# main_sheet.net
KiCad netlist of a schematic drawn in Altium Designer
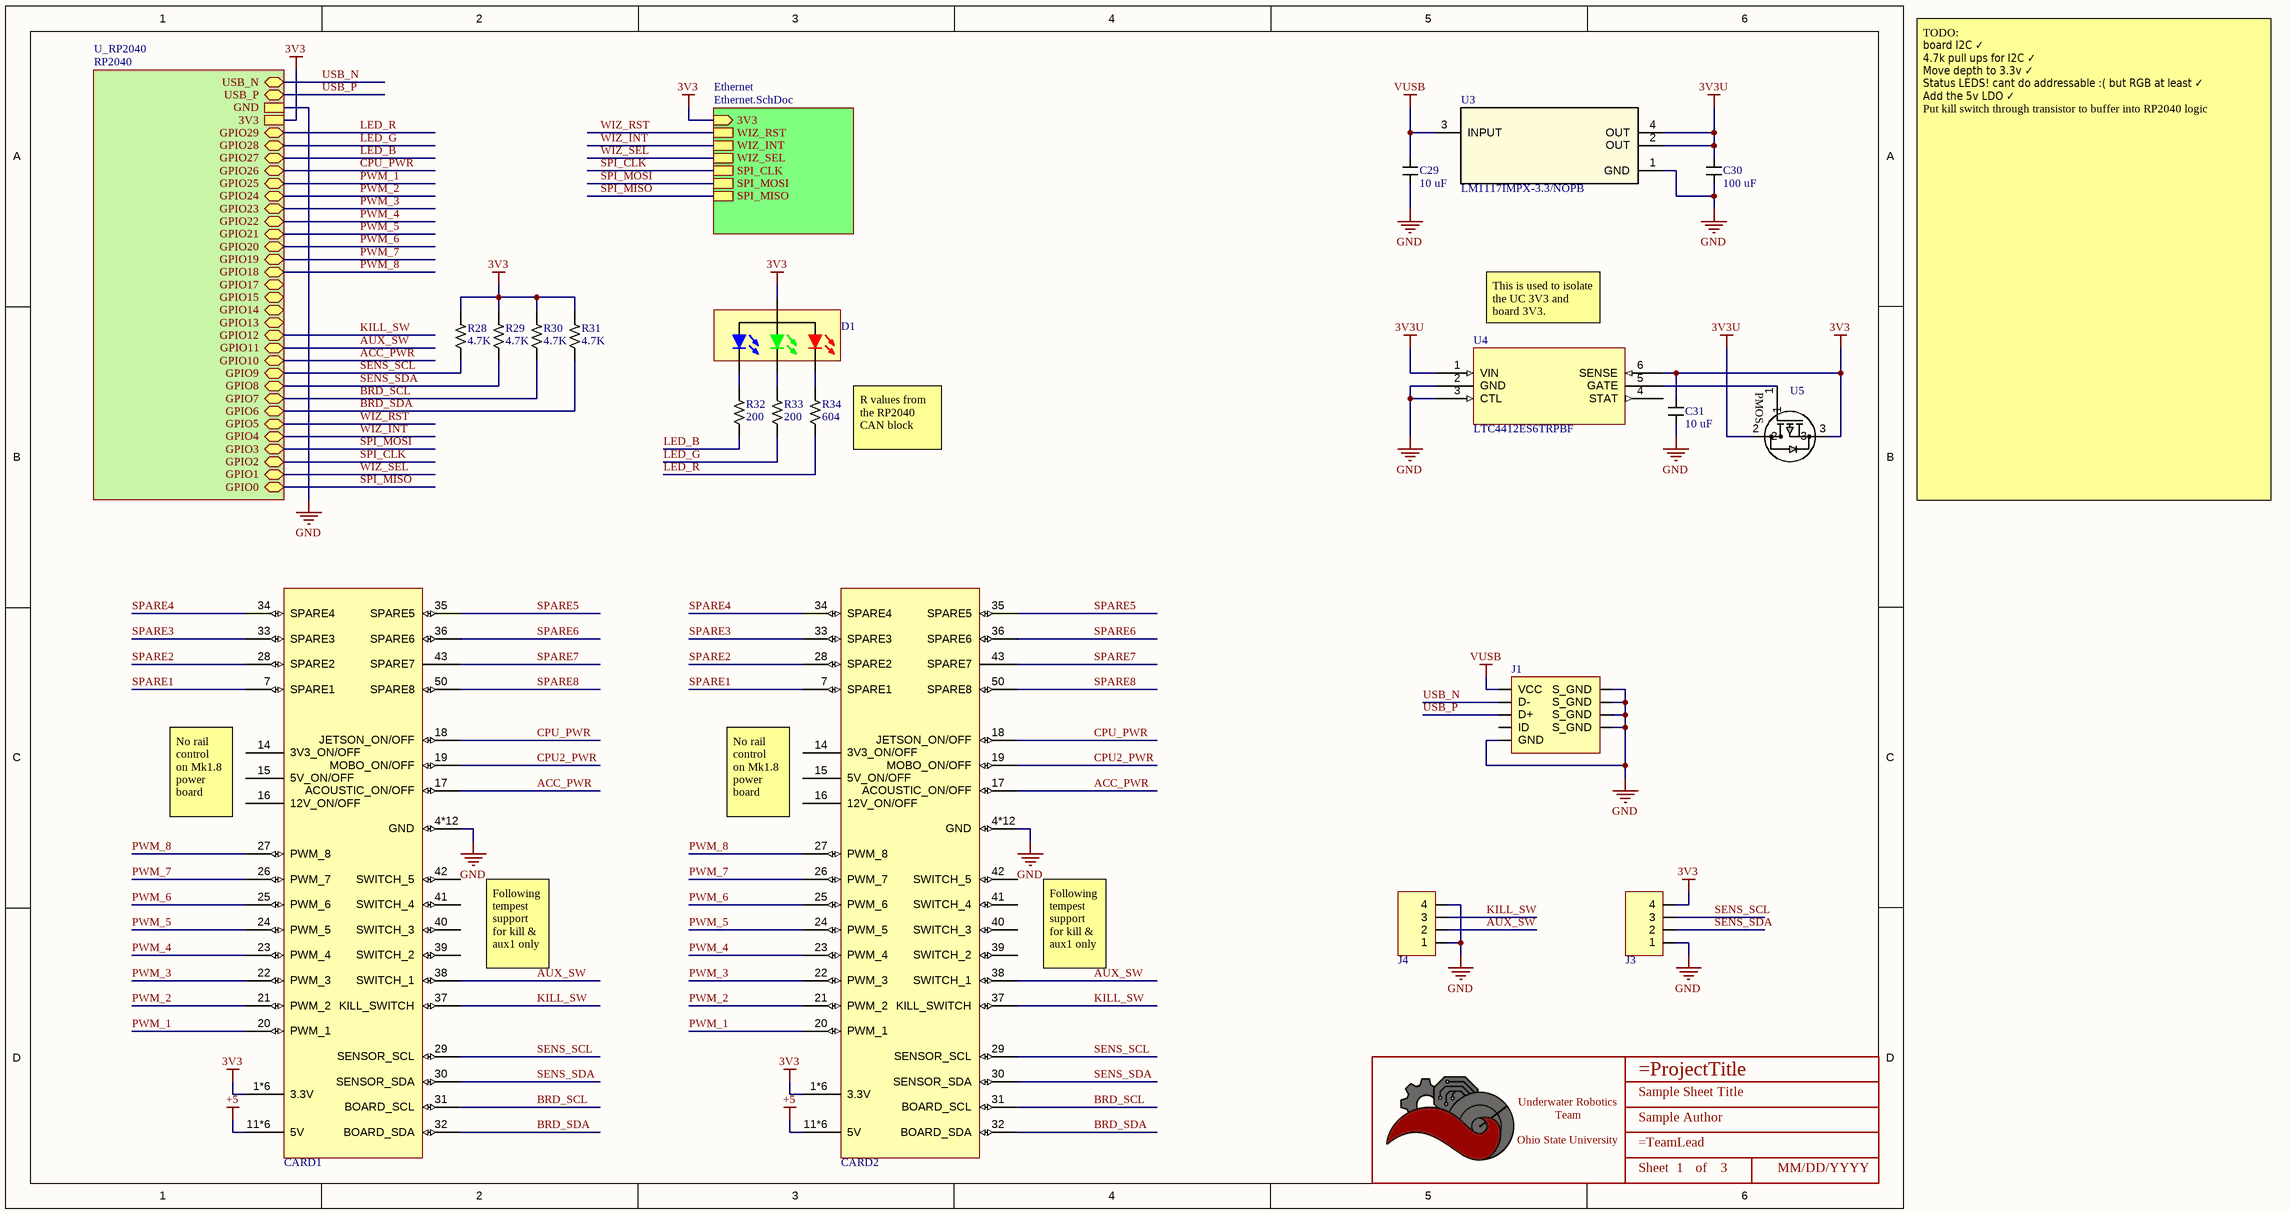
[diagram p0: main_sheet.SchDoc]

(export (version "E")
  (design (tool "Eeschema 10.0.6"))
  (components
    (comp (ref "*")
      (value "Title_Block")
      (footprint "LOGO")
      (description "UWRT Schematic Title Block Template\r\n\r\nCreated June 2021, Dylan Trainor")
      (libsource (lib "UWRT") (part "Title_Block"))
    )
    (comp (ref "C29")
      (value "10uF Ceramic 6.3V")
      (footprint "CAPACITOR_0603")
      (description "Cap 10uF 6.3V +/-20%\r\nCeramic 0603")
      (fields
        (field (name "TOLERANCE") "+/- 20%")
        (field (name "VOLTAGE") "6.3V")
        (field (name "VALUE (UF)") "10 uF")
        (field (name "MADE BY") "Flip B")
      )
      (libsource (lib "Capacitors") (part "CAPACITOR_10uF_0603"))
    )
    (comp (ref "C30")
      (value "100uF Ceramic 6.3V")
      (footprint "CAPACITOR_0603")
      (description "Cap 100uF 6.3V +/-20%\r\nCeramic 0603")
      (fields
        (field (name "TOLERANCE") "+/- 20%")
        (field (name "VOLTAGE") "6.3V")
        (field (name "VALUE (UF)") "100 uF")
        (field (name "MADE BY") "Dylan Trainor")
      )
      (libsource (lib "Capacitors") (part "CAPACITOR_100uF_0603"))
    )
    (comp (ref "C31")
      (value "10uF Ceramic 6.3V")
      (footprint "CAPACITOR_0603")
      (description "Cap 10uF 6.3V +/-20%\r\nCeramic 0603")
      (fields
        (field (name "TOLERANCE") "+/- 20%")
        (field (name "VOLTAGE") "6.3V")
        (field (name "VALUE (UF)") "10 uF")
        (field (name "MADE BY") "Flip B")
      )
      (libsource (lib "Capacitors") (part "CAPACITOR_10uF_0603"))
    )
    (comp (ref "CARD1")
      (value "BACKPLANE_EDGE_SOCKET")
      (footprint "SOCKET_BACKPLANE_EDGE_CONN")
      (description "Backplane Edge Socket")
      (fields (field (name "MADE BY") "Robert Pafford"))
      (libsource (lib "Connectors") (part "BACKPLANE_EDGE_SOCKET"))
    )
    (comp (ref "CARD2")
      (value "BACKPLANE_EDGE_SOCKET")
      (footprint "SOCKET_BACKPLANE_EDGE_CONN")
      (description "Backplane Edge Socket")
      (fields (field (name "MADE BY") "Robert Pafford"))
      (libsource (lib "Connectors") (part "BACKPLANE_EDGE_SOCKET"))
    )
    (comp (ref "D1")
      (value "EAST1616RGBB4")
      (footprint "LED_0606_4SMD")
      (description "LED RGB CLEAR 4SMD")
      (fields (field (name "MADE BY") "Robert Pafford"))
      (libsource (lib "Diodes") (part "LED_RGB_4SMD"))
    )
    (comp (ref "J1")
      (value "USB_MICRO R/A")
      (footprint "CONN_MINIUSB")
      (description "Amphenol Micro USB-B\r\nUSB2.0 5 Pin Right Angle SMD")
      (fields (field (name "MANUFACTURER") "Amphenol") (field (name "CREATED BY") "Flip B"))
      (libsource (lib "Connectors") (part "CONN_MICROUSB"))
    )
    (comp (ref "J3")
      (value "4 POS R/A")
      (footprint "CONN_MOLEX_MINIFIT JR_4 POS_R/A")
      (description "Molex Minifit Jr. 5569 \r\n4 Pos R/A Natural")
      (fields (field (name "MANUFACTURER") "Molex") (field (name "CREATED BY") "Flip B"))
      (libsource (lib "Connectors") (part "CONN_MOLEX_MINIFIT JR_4POS_R/A"))
    )
    (comp (ref "J4")
      (value "4 POS R/A")
      (footprint "CONN_MOLEX_MINIFIT JR_4 POS_R/A")
      (description "Molex Minifit Jr. 5569 \r\n4 Pos R/A Natural")
      (fields (field (name "MANUFACTURER") "Molex") (field (name "CREATED BY") "Flip B"))
      (libsource (lib "Connectors") (part "CONN_MOLEX_MINIFIT JR_4POS_R/A"))
    )
    (comp (ref "R28")
      (value "10k Ohm 5% 1/10W")
      (footprint "RESISTOR_0603")
      (description "RES 10k OHM 5% 1/10W 0603")
      (fields
        (field (name "TOLERANCE") "+/- 5%")
        (field (name "VALUE  (OHMS)") "4.7K")
        (field (name "MADE BY") "Robert Pafford")
      )
      (libsource (lib "Resistors") (part "RESISTOR_10K_0603"))
    )
    (comp (ref "R29")
      (value "10k Ohm 5% 1/10W")
      (footprint "RESISTOR_0603")
      (description "RES 10k OHM 5% 1/10W 0603")
      (fields
        (field (name "TOLERANCE") "+/- 5%")
        (field (name "VALUE  (OHMS)") "4.7K")
        (field (name "MADE BY") "Robert Pafford")
      )
      (libsource (lib "Resistors") (part "RESISTOR_10K_0603"))
    )
    (comp (ref "R30")
      (value "10k Ohm 5% 1/10W")
      (footprint "RESISTOR_0603")
      (description "RES 10k OHM 5% 1/10W 0603")
      (fields
        (field (name "TOLERANCE") "+/- 5%")
        (field (name "VALUE  (OHMS)") "4.7K")
        (field (name "MADE BY") "Robert Pafford")
      )
      (libsource (lib "Resistors") (part "RESISTOR_10K_0603"))
    )
    (comp (ref "R31")
      (value "10k Ohm 5% 1/10W")
      (footprint "RESISTOR_0603")
      (description "RES 10k OHM 5% 1/10W 0603")
      (fields
        (field (name "TOLERANCE") "+/- 5%")
        (field (name "VALUE  (OHMS)") "4.7K")
        (field (name "MADE BY") "Robert Pafford")
      )
      (libsource (lib "Resistors") (part "RESISTOR_10K_0603"))
    )
    (comp (ref "R32")
      (value "10k Ohm 5% 1/10W")
      (footprint "RESISTOR_0603")
      (description "RES 10k OHM 5% 1/10W 0603")
      (fields
        (field (name "TOLERANCE") "+/- 5%")
        (field (name "VALUE  (OHMS)") "200")
        (field (name "MADE BY") "Robert Pafford")
      )
      (libsource (lib "Resistors") (part "RESISTOR_10K_0603"))
    )
    (comp (ref "R33")
      (value "10k Ohm 5% 1/10W")
      (footprint "RESISTOR_0603")
      (description "RES 10k OHM 5% 1/10W 0603")
      (fields
        (field (name "TOLERANCE") "+/- 5%")
        (field (name "VALUE  (OHMS)") "200")
        (field (name "MADE BY") "Robert Pafford")
      )
      (libsource (lib "Resistors") (part "RESISTOR_10K_0603"))
    )
    (comp (ref "R34")
      (value "10k Ohm 5% 1/10W")
      (footprint "RESISTOR_0603")
      (description "RES 10k OHM 5% 1/10W 0603")
      (fields
        (field (name "TOLERANCE") "+/- 5%")
        (field (name "VALUE  (OHMS)") "604")
        (field (name "MADE BY") "Robert Pafford")
      )
      (libsource (lib "Resistors") (part "RESISTOR_10K_0603"))
    )
    (comp (ref "U3")
      (value "LM1117IMPX-3.3/NOPB")
      (footprint "SOT-223-4")
      (description "IC REG LIN 3.3V 800MA SOT223-4")
      (fields
        (field (name "PARTNUMBER") "LM1117IMP-3.3/NOPB")
        (field (name "MANUFACTURER") "Texas Instruments")
        (field (name "CREATED BY") "Dylan T")
      )
      (libsource (lib "Converter") (part "LM1117IMPX-3.3/NOPB"))
    )
    (comp (ref "U4")
      (value "LTC4412ES6TRPBF")
      (footprint "Integrated Circuits:TSOT-23_S6")
      (description "OR Controller Source Selector Switch P-Channel 2:1 TSOT-23-6")
      (fields (field (name "MP") "LTC4412ES6#TRPBF") (field (name "MF") "Analog Devices"))
      (libsource (lib "Integrated Circuits") (part "LTC4412ES6TRPBF"))
    )
    (comp (ref "U5")
      (value "MOSFET P-CHANNEL 20V 4.7A SOT23")
      (footprint "SOT-23-3")
      (description "P-Channel 20 V 4.7A (Tc) 1.56W (Tc) Surface Mount SOT-23")
      (fields
        (field (name "MANUFACTURER_PART_NUMBER") "TSM500P02CX")
        (field (name "CREATED BY") "Robert Pafford")
      )
      (libsource (lib "Transistors") (part "TSM500P02CX"))
    )
  )
  (nets
    (net (code "1") (name "+5") (class "Default")
      (node (ref "CARD1") (pin "11*6") (pinfunction "5V_11*6") (pintype "power_in"))
      (node (ref "CARD2") (pin "11*6") (pinfunction "5V_11*6") (pintype "power_in"))
    )
    (net (code "2") (name "/ACC_PWR") (class "Default")
      (node (ref "CARD1") (pin "17") (pinfunction "ACOUSTIC_ON/OFF_17") (pintype "bidirectional"))
      (node (ref "CARD2") (pin "17") (pinfunction "ACOUSTIC_ON/OFF_17") (pintype "bidirectional"))
    )
    (net (code "3") (name "/AUX_SW") (class "Default")
      (node (ref "CARD1") (pin "38") (pinfunction "SWITCH_1_38") (pintype "bidirectional"))
      (node (ref "CARD2") (pin "38") (pinfunction "SWITCH_1_38") (pintype "bidirectional"))
      (node (ref "J4") (pin "2") (pinfunction "2_2") (pintype "passive"))
    )
    (net (code "4") (name "/BRD_SCL") (class "Default")
      (node (ref "CARD1") (pin "31") (pinfunction "BOARD_SCL_31") (pintype "bidirectional"))
      (node (ref "CARD2") (pin "31") (pinfunction "BOARD_SCL_31") (pintype "bidirectional"))
      (node (ref "R30") (pin "2") (pinfunction "2_2") (pintype "passive"))
    )
    (net (code "5") (name "/BRD_SDA") (class "Default")
      (node (ref "CARD1") (pin "32") (pinfunction "BOARD_SDA_32") (pintype "bidirectional"))
      (node (ref "CARD2") (pin "32") (pinfunction "BOARD_SDA_32") (pintype "bidirectional"))
      (node (ref "R31") (pin "2") (pinfunction "2_2") (pintype "passive"))
    )
    (net (code "6") (name "/CPU2_PWR") (class "Default")
      (node (ref "CARD1") (pin "19") (pinfunction "MOBO_ON/OFF_19") (pintype "bidirectional"))
      (node (ref "CARD2") (pin "19") (pinfunction "MOBO_ON/OFF_19") (pintype "bidirectional"))
    )
    (net (code "7") (name "/CPU_PWR") (class "Default")
      (node (ref "CARD1") (pin "18") (pinfunction "JETSON_ON/OFF_18") (pintype "bidirectional"))
      (node (ref "CARD2") (pin "18") (pinfunction "JETSON_ON/OFF_18") (pintype "bidirectional"))
    )
    (net (code "12") (name "/KILL_SW") (class "Default")
      (node (ref "CARD1") (pin "37") (pinfunction "KILL_SWITCH_37") (pintype "bidirectional"))
      (node (ref "CARD2") (pin "37") (pinfunction "KILL_SWITCH_37") (pintype "bidirectional"))
      (node (ref "J4") (pin "3") (pinfunction "3_3") (pintype "passive"))
    )
    (net (code "13") (name "/LED_B") (class "Default")
      (node (ref "R32") (pin "2") (pinfunction "2_2") (pintype "passive"))
    )
    (net (code "14") (name "/LED_G") (class "Default")
      (node (ref "R33") (pin "2") (pinfunction "2_2") (pintype "passive"))
    )
    (net (code "15") (name "/LED_R") (class "Default")
      (node (ref "R34") (pin "2") (pinfunction "2_2") (pintype "passive"))
    )
    (net (code "16") (name "/PWM_1") (class "Default")
      (node (ref "CARD1") (pin "20") (pinfunction "PWM_1_20") (pintype "bidirectional"))
      (node (ref "CARD2") (pin "20") (pinfunction "PWM_1_20") (pintype "bidirectional"))
    )
    (net (code "17") (name "/PWM_2") (class "Default")
      (node (ref "CARD1") (pin "21") (pinfunction "PWM_2_21") (pintype "bidirectional"))
      (node (ref "CARD2") (pin "21") (pinfunction "PWM_2_21") (pintype "bidirectional"))
    )
    (net (code "18") (name "/PWM_3") (class "Default")
      (node (ref "CARD1") (pin "22") (pinfunction "PWM_3_22") (pintype "bidirectional"))
      (node (ref "CARD2") (pin "22") (pinfunction "PWM_3_22") (pintype "bidirectional"))
    )
    (net (code "19") (name "/PWM_4") (class "Default")
      (node (ref "CARD1") (pin "23") (pinfunction "PWM_4_23") (pintype "bidirectional"))
      (node (ref "CARD2") (pin "23") (pinfunction "PWM_4_23") (pintype "bidirectional"))
    )
    (net (code "20") (name "/PWM_5") (class "Default")
      (node (ref "CARD1") (pin "24") (pinfunction "PWM_5_24") (pintype "bidirectional"))
      (node (ref "CARD2") (pin "24") (pinfunction "PWM_5_24") (pintype "bidirectional"))
    )
    (net (code "21") (name "/PWM_6") (class "Default")
      (node (ref "CARD1") (pin "25") (pinfunction "PWM_6_25") (pintype "bidirectional"))
      (node (ref "CARD2") (pin "25") (pinfunction "PWM_6_25") (pintype "bidirectional"))
    )
    (net (code "22") (name "/PWM_7") (class "Default")
      (node (ref "CARD1") (pin "26") (pinfunction "PWM_7_26") (pintype "bidirectional"))
      (node (ref "CARD2") (pin "26") (pinfunction "PWM_7_26") (pintype "bidirectional"))
    )
    (net (code "23") (name "/PWM_8") (class "Default")
      (node (ref "CARD1") (pin "27") (pinfunction "PWM_8_27") (pintype "bidirectional"))
      (node (ref "CARD2") (pin "27") (pinfunction "PWM_8_27") (pintype "bidirectional"))
    )
    (net (code "24") (name "/SENS_SCL") (class "Default")
      (node (ref "CARD1") (pin "29") (pinfunction "SENSOR_SCL_29") (pintype "bidirectional"))
      (node (ref "CARD2") (pin "29") (pinfunction "SENSOR_SCL_29") (pintype "bidirectional"))
      (node (ref "J3") (pin "3") (pinfunction "3_3") (pintype "passive"))
      (node (ref "R28") (pin "2") (pinfunction "2_2") (pintype "passive"))
    )
    (net (code "25") (name "/SENS_SDA") (class "Default")
      (node (ref "CARD1") (pin "30") (pinfunction "SENSOR_SDA_30") (pintype "bidirectional"))
      (node (ref "CARD2") (pin "30") (pinfunction "SENSOR_SDA_30") (pintype "bidirectional"))
      (node (ref "J3") (pin "2") (pinfunction "2_2") (pintype "passive"))
      (node (ref "R29") (pin "2") (pinfunction "2_2") (pintype "passive"))
    )
    (net (code "26") (name "/SPARE1") (class "Default")
      (node (ref "CARD1") (pin "7") (pinfunction "SPARE1_7") (pintype "bidirectional"))
      (node (ref "CARD2") (pin "7") (pinfunction "SPARE1_7") (pintype "bidirectional"))
    )
    (net (code "27") (name "/SPARE2") (class "Default")
      (node (ref "CARD1") (pin "28") (pinfunction "SPARE2_28") (pintype "bidirectional"))
      (node (ref "CARD2") (pin "28") (pinfunction "SPARE2_28") (pintype "bidirectional"))
    )
    (net (code "28") (name "/SPARE3") (class "Default")
      (node (ref "CARD1") (pin "33") (pinfunction "SPARE3_33") (pintype "bidirectional"))
      (node (ref "CARD2") (pin "33") (pinfunction "SPARE3_33") (pintype "bidirectional"))
    )
    (net (code "29") (name "/SPARE4") (class "Default")
      (node (ref "CARD1") (pin "34") (pinfunction "SPARE4_34") (pintype "bidirectional"))
      (node (ref "CARD2") (pin "34") (pinfunction "SPARE4_34") (pintype "bidirectional"))
    )
    (net (code "30") (name "/SPARE5") (class "Default")
      (node (ref "CARD1") (pin "35") (pinfunction "SPARE5_35") (pintype "bidirectional"))
      (node (ref "CARD2") (pin "35") (pinfunction "SPARE5_35") (pintype "bidirectional"))
    )
    (net (code "31") (name "/SPARE6") (class "Default")
      (node (ref "CARD1") (pin "36") (pinfunction "SPARE6_36") (pintype "bidirectional"))
      (node (ref "CARD2") (pin "36") (pinfunction "SPARE6_36") (pintype "bidirectional"))
    )
    (net (code "32") (name "/SPARE7") (class "Default")
      (node (ref "CARD1") (pin "43") (pinfunction "SPARE7_43") (pintype "power_in"))
      (node (ref "CARD2") (pin "43") (pinfunction "SPARE7_43") (pintype "power_in"))
    )
    (net (code "33") (name "/SPARE8") (class "Default")
      (node (ref "CARD1") (pin "50") (pinfunction "SPARE8_50") (pintype "bidirectional"))
      (node (ref "CARD2") (pin "50") (pinfunction "SPARE8_50") (pintype "bidirectional"))
    )
    (net (code "37") (name "/USB_N") (class "Default")
      (node (ref "J1") (pin "2") (pinfunction "D-_2") (pintype "passive"))
    )
    (net (code "38") (name "/USB_P") (class "Default")
      (node (ref "J1") (pin "3") (pinfunction "D+_3") (pintype "passive"))
    )
    (net (code "42") (name "3V3") (class "Default")
      (node (ref "C31") (pin "1") (pinfunction "1_1") (pintype "passive"))
      (node (ref "CARD1") (pin "1*6") (pinfunction "3.3V_1*6") (pintype "power_in"))
      (node (ref "CARD2") (pin "1*6") (pinfunction "3.3V_1*6") (pintype "power_in"))
      (node (ref "D1") (pin "4") (pinfunction "4_4") (pintype "passive"))
      (node (ref "J3") (pin "4") (pinfunction "4_4") (pintype "passive"))
      (node (ref "R28") (pin "1") (pinfunction "1_1") (pintype "passive"))
      (node (ref "R29") (pin "1") (pinfunction "1_1") (pintype "passive"))
      (node (ref "R30") (pin "1") (pinfunction "1_1") (pintype "passive"))
      (node (ref "R31") (pin "1") (pinfunction "1_1") (pintype "passive"))
      (node (ref "U4") (pin "6") (pinfunction "SENSE_6") (pintype "input"))
      (node (ref "U5") (pin "3") (pinfunction "3_3") (pintype "passive"))
    )
    (net (code "43") (name "3V3U") (class "Default")
      (node (ref "C30") (pin "1") (pinfunction "1_1") (pintype "passive"))
      (node (ref "U3") (pin "2") (pinfunction "OUT_2") (pintype "power_in"))
      (node (ref "U3") (pin "4") (pinfunction "OUT_4") (pintype "power_in"))
      (node (ref "U4") (pin "1") (pinfunction "VIN_1") (pintype "input"))
      (node (ref "U5") (pin "2") (pinfunction "2_2") (pintype "passive"))
    )
    (net (code "44") (name "GND") (class "Default")
      (node (ref "C29") (pin "2") (pinfunction "2_2") (pintype "passive"))
      (node (ref "C30") (pin "2") (pinfunction "2_2") (pintype "passive"))
      (node (ref "C31") (pin "2") (pinfunction "2_2") (pintype "passive"))
      (node (ref "CARD1") (pin "4*12") (pinfunction "GND_4*12") (pintype "bidirectional"))
      (node (ref "CARD2") (pin "4*12") (pinfunction "GND_4*12") (pintype "bidirectional"))
      (node (ref "J1") (pin "5") (pinfunction "GND_5") (pintype "passive"))
      (node (ref "J1") (pin "6") (pinfunction "S_GND_6") (pintype "passive"))
      (node (ref "J1") (pin "7") (pinfunction "S_GND_7") (pintype "passive"))
      (node (ref "J1") (pin "8") (pinfunction "S_GND_8") (pintype "passive"))
      (node (ref "J1") (pin "9") (pinfunction "S_GND_9") (pintype "passive"))
      (node (ref "J3") (pin "1") (pinfunction "1_1") (pintype "passive"))
      (node (ref "J4") (pin "1") (pinfunction "1_1") (pintype "passive"))
      (node (ref "J4") (pin "4") (pinfunction "4_4") (pintype "passive"))
      (node (ref "U3") (pin "1") (pinfunction "GND_1") (pintype "power_in"))
      (node (ref "U4") (pin "2") (pinfunction "GND_2") (pintype "power_in"))
      (node (ref "U4") (pin "3") (pinfunction "CTL_3") (pintype "input"))
    )
    (net (code "45") (name "Net-(D1-32)") (class "Default")
      (node (ref "D1") (pin "3") (pinfunction "32_3") (pintype "passive"))
      (node (ref "R32") (pin "1") (pinfunction "1_1") (pintype "passive"))
    )
    (net (code "46") (name "Net-(D1-Pad1)") (class "Default")
      (node (ref "D1") (pin "1") (pinfunction "1_1") (pintype "passive"))
      (node (ref "R34") (pin "1") (pinfunction "1_1") (pintype "passive"))
    )
    (net (code "47") (name "Net-(D1-Pad2)") (class "Default")
      (node (ref "D1") (pin "2") (pinfunction "2_2") (pintype "passive"))
      (node (ref "R33") (pin "1") (pinfunction "1_1") (pintype "passive"))
    )
    (net (code "48") (name "Net-(U4-GATE)") (class "Default")
      (node (ref "U4") (pin "5") (pinfunction "GATE_5") (pintype "passive"))
      (node (ref "U5") (pin "1") (pinfunction "1_1") (pintype "passive"))
    )
    (net (code "49") (name "VUSB") (class "Default")
      (node (ref "C29") (pin "1") (pinfunction "1_1") (pintype "passive"))
      (node (ref "J1") (pin "1") (pinfunction "VCC_1") (pintype "passive"))
      (node (ref "U3") (pin "3") (pinfunction "INPUT_3") (pintype "power_in"))
    )
    (net (code "50") (name "unconnected-(CARD1-3V3_ON{slash}OFF-Pad14)") (class "Default")
      (node (ref "CARD1") (pin "14") (pinfunction "3V3_ON/OFF_14") (pintype "power_in"))
    )
    (net (code "51") (name "unconnected-(CARD1-5V_ON{slash}OFF-Pad15)") (class "Default")
      (node (ref "CARD1") (pin "15") (pinfunction "5V_ON/OFF_15") (pintype "power_in"))
    )
    (net (code "52") (name "unconnected-(CARD1-12V_ON{slash}OFF-Pad16)") (class "Default")
      (node (ref "CARD1") (pin "16") (pinfunction "12V_ON/OFF_16") (pintype "power_in"))
    )
    (net (code "53") (name "unconnected-(CARD1-SWITCH_2-Pad39)") (class "Default")
      (node (ref "CARD1") (pin "39") (pinfunction "SWITCH_2_39") (pintype "bidirectional"))
    )
    (net (code "54") (name "unconnected-(CARD1-SWITCH_3-Pad40)") (class "Default")
      (node (ref "CARD1") (pin "40") (pinfunction "SWITCH_3_40") (pintype "bidirectional"))
    )
    (net (code "55") (name "unconnected-(CARD1-SWITCH_4-Pad41)") (class "Default")
      (node (ref "CARD1") (pin "41") (pinfunction "SWITCH_4_41") (pintype "bidirectional"))
    )
    (net (code "56") (name "unconnected-(CARD1-SWITCH_5-Pad42)") (class "Default")
      (node (ref "CARD1") (pin "42") (pinfunction "SWITCH_5_42") (pintype "bidirectional"))
    )
    (net (code "57") (name "unconnected-(CARD2-3V3_ON{slash}OFF-Pad14)") (class "Default")
      (node (ref "CARD2") (pin "14") (pinfunction "3V3_ON/OFF_14") (pintype "power_in"))
    )
    (net (code "58") (name "unconnected-(CARD2-5V_ON{slash}OFF-Pad15)") (class "Default")
      (node (ref "CARD2") (pin "15") (pinfunction "5V_ON/OFF_15") (pintype "power_in"))
    )
    (net (code "59") (name "unconnected-(CARD2-12V_ON{slash}OFF-Pad16)") (class "Default")
      (node (ref "CARD2") (pin "16") (pinfunction "12V_ON/OFF_16") (pintype "power_in"))
    )
    (net (code "60") (name "unconnected-(CARD2-SWITCH_2-Pad39)") (class "Default")
      (node (ref "CARD2") (pin "39") (pinfunction "SWITCH_2_39") (pintype "bidirectional"))
    )
    (net (code "61") (name "unconnected-(CARD2-SWITCH_3-Pad40)") (class "Default")
      (node (ref "CARD2") (pin "40") (pinfunction "SWITCH_3_40") (pintype "bidirectional"))
    )
    (net (code "62") (name "unconnected-(CARD2-SWITCH_4-Pad41)") (class "Default")
      (node (ref "CARD2") (pin "41") (pinfunction "SWITCH_4_41") (pintype "bidirectional"))
    )
    (net (code "63") (name "unconnected-(CARD2-SWITCH_5-Pad42)") (class "Default")
      (node (ref "CARD2") (pin "42") (pinfunction "SWITCH_5_42") (pintype "bidirectional"))
    )
    (net (code "64") (name "unconnected-(J1-ID-Pad4)") (class "Default")
      (node (ref "J1") (pin "4") (pinfunction "ID_4") (pintype "passive"))
    )
    (net (code "65") (name "unconnected-(U4-STAT-Pad4)") (class "Default")
      (node (ref "U4") (pin "4") (pinfunction "STAT_4") (pintype "output"))
    )
  )
)
